# HHO.net
KiCad netlist of a schematic drawn in Altium Designer
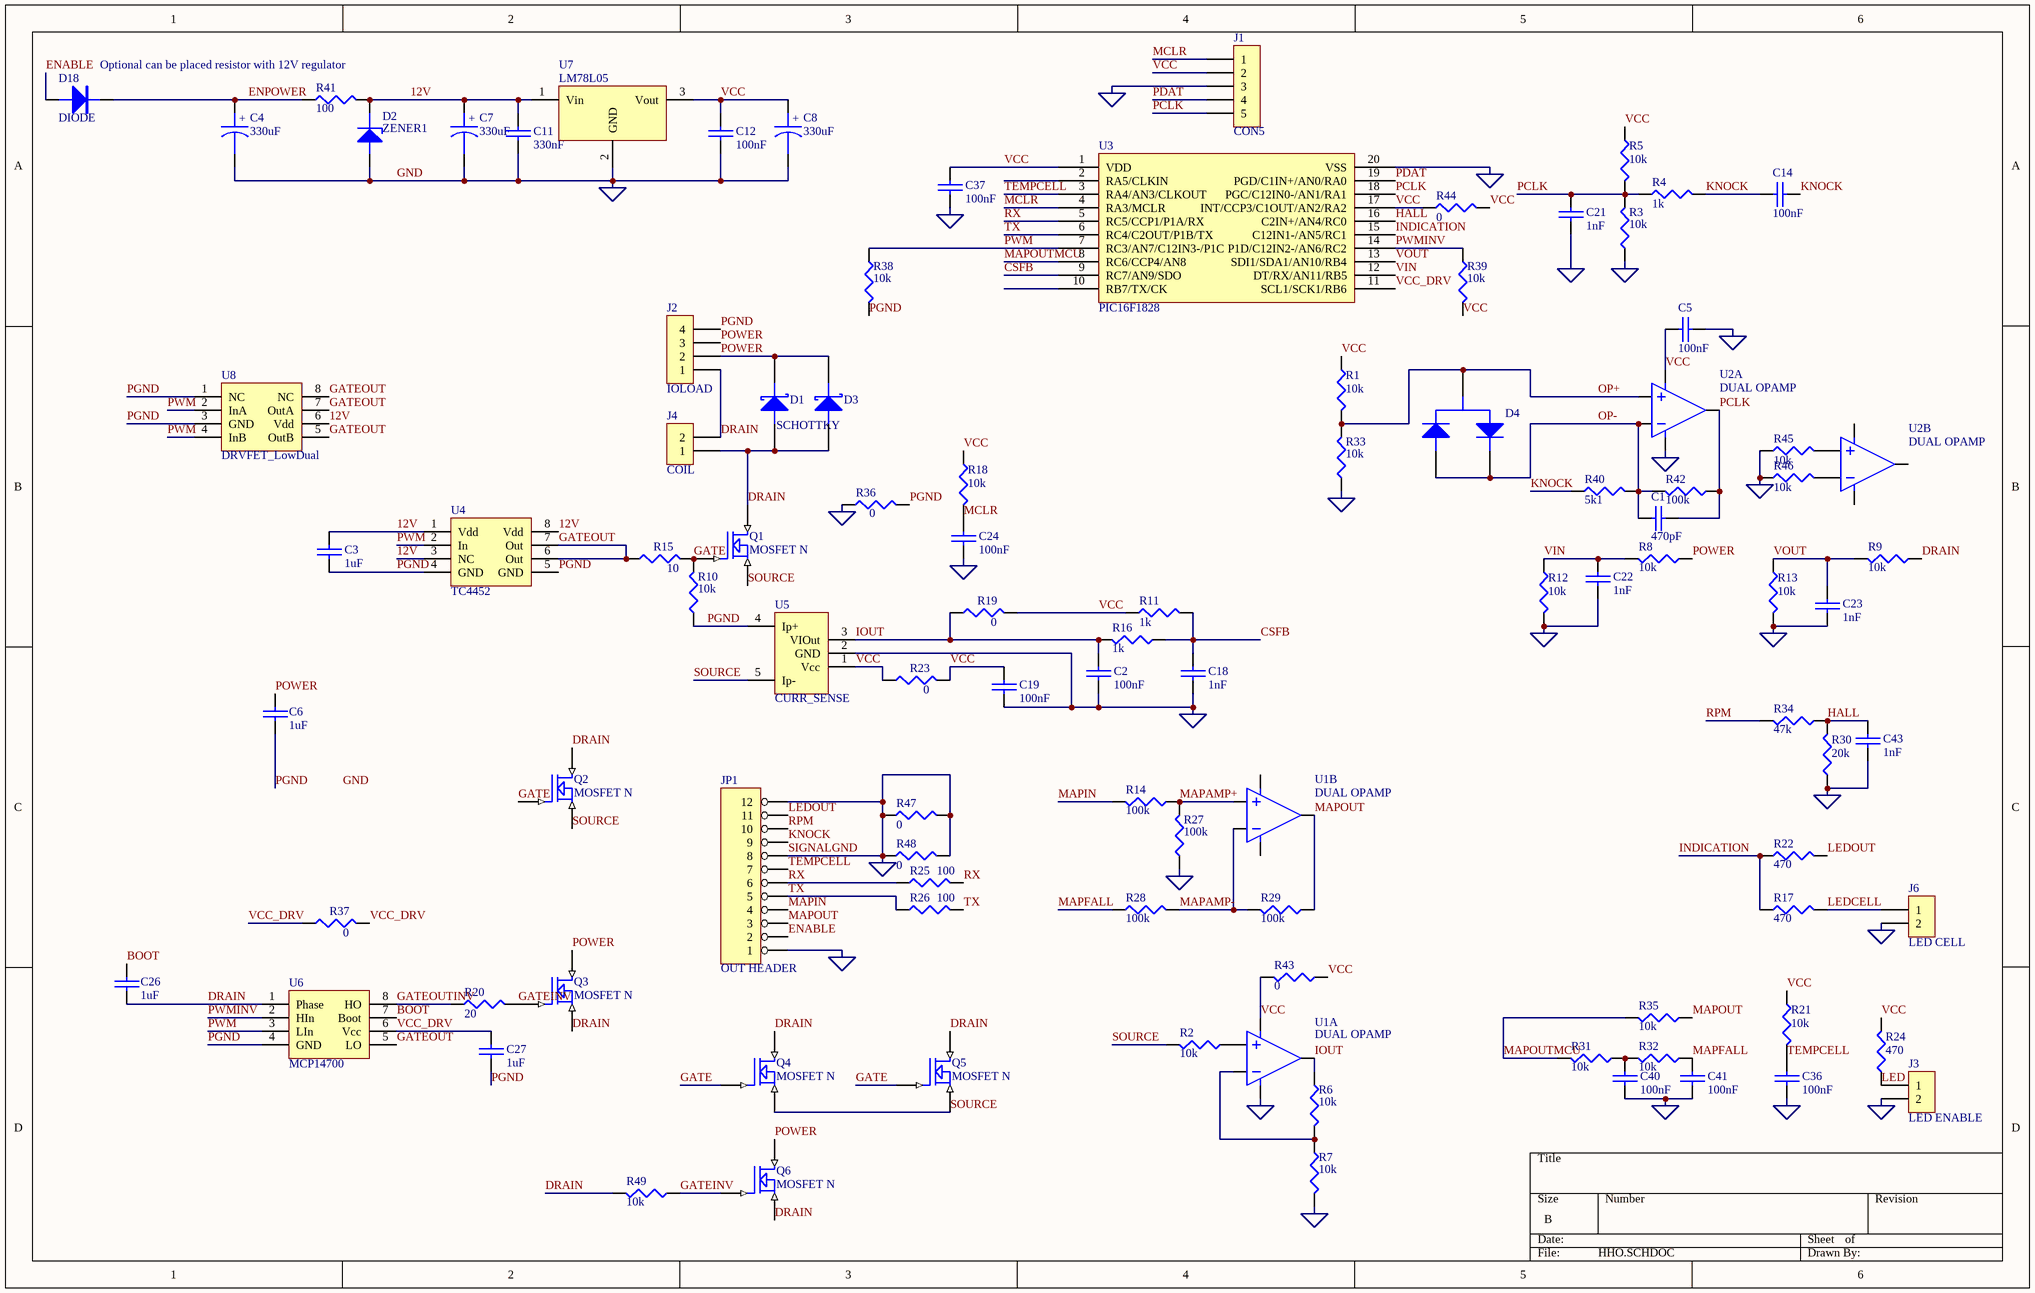
[diagram p0: HHO.SCHDOC]

(export (version "E")
  (design (tool "Eeschema 10.0.6"))
  (components
    (comp (ref "C1")
      (value "470pF")
      (footprint "0603 CAP")
      (description "Capacitor")
      (libsource (lib "*") (part "CAP"))
    )
    (comp (ref "C2")
      (value "100nF")
      (footprint "0603 CAP")
      (description "Capacitor")
      (libsource (lib "*") (part "CAP"))
    )
    (comp (ref "C3")
      (value "1uF")
      (footprint "0805")
      (description "Capacitor")
      (libsource (lib "*") (part "CAP"))
    )
    (comp (ref "C4")
      (value "330uF")
      (footprint "RA 6.3MM")
      (description "Capacitor")
      (libsource (lib "*") (part "CAPACITOR POL"))
    )
    (comp (ref "C5")
      (value "100nF")
      (footprint "0603 CAP")
      (description "Capacitor")
      (libsource (lib "*") (part "CAP"))
    )
    (comp (ref "C6")
      (value "1uF")
      (footprint "1210")
      (description "Capacitor")
      (libsource (lib "*") (part "CAP"))
    )
    (comp (ref "C7")
      (value "330uF")
      (footprint "3528 + RA 6.3mm NOT ROUND")
      (description "Capacitor")
      (libsource (lib "*") (part "CAPACITOR POL"))
    )
    (comp (ref "C8")
      (value "330uF")
      (footprint "3528 + RA 6.3mm NOT ROUND")
      (description "Capacitor")
      (libsource (lib "*") (part "CAPACITOR POL"))
    )
    (comp (ref "C11")
      (value "330nF")
      (footprint "0805")
      (description "Capacitor")
      (libsource (lib "*") (part "CAP"))
    )
    (comp (ref "C12")
      (value "100nF")
      (footprint "0805")
      (description "Capacitor")
      (libsource (lib "*") (part "CAP"))
    )
    (comp (ref "C14")
      (value "100nF")
      (footprint "0603 CAP")
      (description "Capacitor")
      (libsource (lib "*") (part "CAP"))
    )
    (comp (ref "C18")
      (value "1nF")
      (footprint "0603 CAP")
      (description "Capacitor")
      (libsource (lib "*") (part "CAP"))
    )
    (comp (ref "C19")
      (value "100nF")
      (footprint "0603 CAP")
      (description "Capacitor")
      (libsource (lib "*") (part "CAP"))
    )
    (comp (ref "C21")
      (value "1nF")
      (footprint "0603 CAP")
      (description "Capacitor")
      (libsource (lib "*") (part "CAP"))
    )
    (comp (ref "C22")
      (value "1nF")
      (footprint "0603 CAP")
      (description "Capacitor")
      (libsource (lib "*") (part "CAP"))
    )
    (comp (ref "C23")
      (value "1nF")
      (footprint "0603 CAP")
      (description "Capacitor")
      (libsource (lib "*") (part "CAP"))
    )
    (comp (ref "C24")
      (value "100nF")
      (footprint "0603 CAP")
      (description "Capacitor")
      (libsource (lib "*") (part "CAP"))
    )
    (comp (ref "C26")
      (value "1uF")
      (footprint "0805")
      (description "Capacitor")
      (libsource (lib "*") (part "CAP"))
    )
    (comp (ref "C27")
      (value "1uF")
      (footprint "1005")
      (description "Capacitor")
      (libsource (lib "*") (part "CAP"))
    )
    (comp (ref "C36")
      (value "100nF")
      (footprint "0603 CAP")
      (description "Capacitor")
      (libsource (lib "*") (part "CAP"))
    )
    (comp (ref "C37")
      (value "100nF")
      (footprint "0603 CAP")
      (description "Capacitor")
      (libsource (lib "*") (part "CAP"))
    )
    (comp (ref "C40")
      (value "100nF")
      (footprint "0603 CAP")
      (description "Capacitor")
      (libsource (lib "*") (part "CAP"))
    )
    (comp (ref "C41")
      (value "100nF")
      (footprint "0603 CAP")
      (description "Capacitor")
      (libsource (lib "*") (part "CAP"))
    )
    (comp (ref "C43")
      (value "1nF")
      (footprint "0603 CAP")
      (description "Capacitor")
      (libsource (lib "*") (part "CAP"))
    )
    (comp (ref "D1")
      (value "SCHOTTKY")
      (footprint "D2-Pack - 3 - DIODE")
      (description "Schottky Diode")
      (libsource (lib "Miscellaneous Devices") (part "DIODE SCHOTTKY"))
    )
    (comp (ref "D2")
      (value "ZENER1")
      (footprint "SIP2")
      (description "Zener Diode")
      (libsource (lib "Miscellaneous Devices") (part "ZENER1"))
    )
    (comp (ref "D3")
      (value "~")
      (footprint "D2-Pack - 3 - DIODE")
      (description "Schottky Diode")
      (libsource (lib "Miscellaneous Devices") (part "DIODE SCHOTTKY"))
    )
    (comp (ref "D4")
      (value "DUAL DIODE BAV99")
      (footprint "SOT-23")
      (libsource (lib "Devices") (part "DUAL DIODE BAV99"))
    )
    (comp (ref "D18")
      (value "DIODE")
      (footprint "SIP2")
      (description "Diode")
      (libsource (lib "Miscellaneous Devices") (part "DIODE"))
    )
    (comp (ref "J1")
      (value "CON5")
      (footprint "SIP5")
      (description "Connector")
      (libsource (lib "Miscellaneous Devices") (part "CON5"))
    )
    (comp (ref "J2")
      (value "IOLOAD")
      (footprint "HD 11mm 4P HAMMOND")
      (description "Connector")
      (libsource (lib "Miscellaneous Devices") (part "CON4"))
    )
    (comp (ref "J3")
      (value "LED ENABLE")
      (footprint "SIP2")
      (description "Connector")
      (libsource (lib "Miscellaneous Devices") (part "CON2"))
    )
    (comp (ref "J4")
      (value "COIL")
      (footprint "SIP2 - INDUCTOR 20A")
      (description "Connector")
      (libsource (lib "") (part "CON2_1"))
    )
    (comp (ref "J6")
      (value "LED CELL")
      (footprint "SIP2")
      (description "Connector")
      (libsource (lib "Miscellaneous Devices") (part "CON2"))
    )
    (comp (ref "JP1")
      (value "OUT HEADER")
      (footprint "PWD12R")
      (description "12 Pin Header")
      (libsource (lib "Miscellaneous Devices") (part "12 HEADER"))
    )
    (comp (ref "Q1")
      (value "MOSFET N")
      (footprint "D2-Pack - 7")
      (libsource (lib "Miscellaneous Devices") (part "MOSFET N"))
    )
    (comp (ref "Q2")
      (value "MOSFET N")
      (footprint "D2-Pack - 7")
      (libsource (lib "Miscellaneous Devices") (part "MOSFET N"))
    )
    (comp (ref "Q3")
      (value "MOSFET N")
      (footprint "D2-Pack - 7")
      (libsource (lib "Miscellaneous Devices") (part "MOSFET N"))
    )
    (comp (ref "Q4")
      (value "MOSFET N")
      (footprint "TO220")
      (libsource (lib "Miscellaneous Devices") (part "MOSFET N"))
    )
    (comp (ref "Q5")
      (value "MOSFET N")
      (footprint "TO220")
      (libsource (lib "Miscellaneous Devices") (part "MOSFET N"))
    )
    (comp (ref "Q6")
      (value "MOSFET N")
      (footprint "TO220")
      (libsource (lib "Miscellaneous Devices") (part "MOSFET N"))
    )
    (comp (ref "R1") (value "10k") (footprint "1005") (libsource (lib "Miscellaneous Devices") (part "RES1")))
    (comp (ref "R2")
      (value "10k")
      (footprint "0603 RES")
      (libsource (lib "Miscellaneous Devices") (part "RES1"))
    )
    (comp (ref "R3")
      (value "10k")
      (footprint "0603 RES")
      (libsource (lib "Miscellaneous Devices") (part "RES1"))
    )
    (comp (ref "R4")
      (value "1k")
      (footprint "0603 RES")
      (libsource (lib "Miscellaneous Devices") (part "RES1"))
    )
    (comp (ref "R5")
      (value "10k")
      (footprint "0603 RES")
      (libsource (lib "Miscellaneous Devices") (part "RES1"))
    )
    (comp (ref "R6")
      (value "10k")
      (footprint "0603 RES")
      (libsource (lib "Miscellaneous Devices") (part "RES1"))
    )
    (comp (ref "R7")
      (value "10k")
      (footprint "0603 RES")
      (libsource (lib "Miscellaneous Devices") (part "RES1"))
    )
    (comp (ref "R8")
      (value "10k")
      (footprint "0603 RES")
      (libsource (lib "Miscellaneous Devices") (part "RES1"))
    )
    (comp (ref "R9") (value "10k") (footprint "1005") (libsource (lib "Miscellaneous Devices") (part "RES1")))
    (comp (ref "R10")
      (value "10k")
      (footprint "0603 RES")
      (libsource (lib "Miscellaneous Devices") (part "RES1"))
    )
    (comp (ref "R11")
      (value "1k")
      (footprint "0603 RES")
      (libsource (lib "Miscellaneous Devices") (part "RES1"))
    )
    (comp (ref "R12")
      (value "10k")
      (footprint "0603 RES")
      (libsource (lib "Miscellaneous Devices") (part "RES1"))
    )
    (comp (ref "R13")
      (value "10k")
      (footprint "0603")
      (libsource (lib "Miscellaneous Devices") (part "RES1"))
    )
    (comp (ref "R14")
      (value "100k")
      (footprint "0603 RES")
      (libsource (lib "Miscellaneous Devices") (part "RES1"))
    )
    (comp (ref "R15")
      (value "10")
      (footprint "0603 RES")
      (libsource (lib "Miscellaneous Devices") (part "RES1"))
    )
    (comp (ref "R16")
      (value "1k")
      (footprint "0603 RES")
      (libsource (lib "Miscellaneous Devices") (part "RES1"))
    )
    (comp (ref "R17")
      (value "470")
      (footprint "0603 RES")
      (libsource (lib "Miscellaneous Devices") (part "RES1"))
    )
    (comp (ref "R18")
      (value "10k")
      (footprint "0603 RES")
      (libsource (lib "Miscellaneous Devices") (part "RES1"))
    )
    (comp (ref "R19")
      (value "0")
      (footprint "0603 RES")
      (libsource (lib "Miscellaneous Devices") (part "RES1"))
    )
    (comp (ref "R20")
      (value "20")
      (footprint "0603 RES")
      (libsource (lib "Miscellaneous Devices") (part "RES1"))
    )
    (comp (ref "R21")
      (value "10k")
      (footprint "0603 RES")
      (libsource (lib "Miscellaneous Devices") (part "RES1"))
    )
    (comp (ref "R22")
      (value "470")
      (footprint "0603 RES")
      (libsource (lib "Miscellaneous Devices") (part "RES1"))
    )
    (comp (ref "R23")
      (value "0")
      (footprint "0603 RES")
      (libsource (lib "Miscellaneous Devices") (part "RES1"))
    )
    (comp (ref "R24")
      (value "470")
      (footprint "0603 RES")
      (libsource (lib "Miscellaneous Devices") (part "RES1"))
    )
    (comp (ref "R25")
      (value "100")
      (footprint "0603 RES")
      (libsource (lib "Miscellaneous Devices") (part "RES1"))
    )
    (comp (ref "R26")
      (value "100")
      (footprint "0603 RES")
      (libsource (lib "Miscellaneous Devices") (part "RES1"))
    )
    (comp (ref "R27")
      (value "100k")
      (footprint "0603 RES")
      (libsource (lib "Miscellaneous Devices") (part "RES1"))
    )
    (comp (ref "R28")
      (value "100k")
      (footprint "0603 RES")
      (libsource (lib "Miscellaneous Devices") (part "RES1"))
    )
    (comp (ref "R29")
      (value "100k")
      (footprint "0603 RES")
      (libsource (lib "Miscellaneous Devices") (part "RES1"))
    )
    (comp (ref "R30")
      (value "20k")
      (footprint "0603 RES")
      (libsource (lib "Miscellaneous Devices") (part "RES1"))
    )
    (comp (ref "R31")
      (value "10k")
      (footprint "0603 RES")
      (libsource (lib "Miscellaneous Devices") (part "RES1"))
    )
    (comp (ref "R32")
      (value "10k")
      (footprint "0603 RES")
      (libsource (lib "Miscellaneous Devices") (part "RES1"))
    )
    (comp (ref "R33")
      (value "10k")
      (footprint "0603 RES")
      (libsource (lib "Miscellaneous Devices") (part "RES1"))
    )
    (comp (ref "R34")
      (value "47k")
      (footprint "0603 RES")
      (libsource (lib "Miscellaneous Devices") (part "RES1"))
    )
    (comp (ref "R35")
      (value "10k")
      (footprint "0603 RES")
      (libsource (lib "Miscellaneous Devices") (part "RES1"))
    )
    (comp (ref "R36") (value "0") (footprint "0805") (libsource (lib "Miscellaneous Devices") (part "RES1")))
    (comp (ref "R37")
      (value "0")
      (footprint "0603 RES")
      (libsource (lib "Miscellaneous Devices") (part "RES1"))
    )
    (comp (ref "R38")
      (value "10k")
      (footprint "0603 RES")
      (libsource (lib "Miscellaneous Devices") (part "RES1"))
    )
    (comp (ref "R39")
      (value "10k")
      (footprint "0603 RES")
      (libsource (lib "Miscellaneous Devices") (part "RES1"))
    )
    (comp (ref "R40")
      (value "5k1")
      (footprint "0603 RES")
      (libsource (lib "Miscellaneous Devices") (part "RES1"))
    )
    (comp (ref "R41")
      (value "100")
      (footprint "0805")
      (libsource (lib "Miscellaneous Devices") (part "RES1"))
    )
    (comp (ref "R42")
      (value "100k")
      (footprint "0603 RES")
      (libsource (lib "Miscellaneous Devices") (part "RES1"))
    )
    (comp (ref "R43")
      (value "0")
      (footprint "0603 RES")
      (libsource (lib "Miscellaneous Devices") (part "RES1"))
    )
    (comp (ref "R44")
      (value "0")
      (footprint "0603 RES")
      (libsource (lib "Miscellaneous Devices") (part "RES1"))
    )
    (comp (ref "R45")
      (value "10k")
      (footprint "0603 RES")
      (libsource (lib "Miscellaneous Devices") (part "RES1"))
    )
    (comp (ref "R46")
      (value "10k")
      (footprint "0603 RES")
      (libsource (lib "Miscellaneous Devices") (part "RES1"))
    )
    (comp (ref "R47")
      (value "0")
      (footprint "0603 RES")
      (libsource (lib "Miscellaneous Devices") (part "RES1"))
    )
    (comp (ref "R48")
      (value "0")
      (footprint "0603 RES")
      (libsource (lib "Miscellaneous Devices") (part "RES1"))
    )
    (comp (ref "R49")
      (value "10k")
      (footprint "0603 RES")
      (libsource (lib "Miscellaneous Devices") (part "RES1"))
    )
    (comp (ref "U1") (value "DUAL OPAMP") (footprint "SO-8") (libsource (lib "Devices") (part "DUAL OPAMP")))
    (comp (ref "U2") (value "DUAL OPAMP") (footprint "SO-8") (libsource (lib "Devices") (part "DUAL OPAMP")))
    (comp (ref "U3")
      (value "PIC16F1828")
      (footprint "SOIC20WIDE")
      (description "Microchip Microcontroller")
      (libsource (lib "MCU") (part "PIC16F1828"))
    )
    (comp (ref "U4")
      (value "TC4452")
      (footprint "SO-8")
      (description "Mosfet Low Side Single driver")
      (libsource (lib "Devices") (part "DRVFET_LowSingle"))
    )
    (comp (ref "U5")
      (value "CURR_SENSE")
      (footprint "5-CB WIDE")
      (description "Current Sense Hall")
      (libsource (lib "Devices") (part "CURR_SENSE"))
    )
    (comp (ref "U6")
      (value "MCP14700")
      (footprint "SO-8")
      (description "Mosfet High and Low Side driver")
      (libsource (lib "Devices") (part "DRVFET_14700"))
    )
    (comp (ref "U7") (value "LM78L05") (footprint "TO-92 WIDE") (libsource (lib "*") (part "VOLTREG")))
    (comp (ref "U8")
      (value "DRVFET_LowDual")
      (footprint "SO-8")
      (description "Mosfet Low Side Dual driver")
      (libsource (lib "Devices") (part "DRVFET_LowDual"))
    )
  )
  (nets
    (net (code "1") (name "/12V") (class "Default")
      (node (ref "C11") (pin "1") (pinfunction "1_1") (pintype "passive"))
      (node (ref "C3") (pin "1") (pinfunction "1_1") (pintype "passive"))
      (node (ref "C7") (pin "1") (pinfunction "1_1") (pintype "passive"))
      (node (ref "D2") (pin "2") (pinfunction "K_2") (pintype "passive"))
      (node (ref "R41") (pin "2") (pinfunction "2_2") (pintype "passive"))
      (node (ref "U4") (pin "1") (pinfunction "Vdd_1") (pintype "passive"))
      (node (ref "U4") (pin "3") (pinfunction "NC_3") (pintype "passive"))
      (node (ref "U4") (pin "8") (pinfunction "Vdd_8") (pintype "passive"))
      (node (ref "U7") (pin "1") (pinfunction "Vin_1") (pintype "passive"))
      (node (ref "U8") (pin "6") (pinfunction "Vdd_6") (pintype "passive"))
    )
    (net (code "2") (name "/BOOT") (class "Default")
      (node (ref "C26") (pin "1") (pinfunction "1_1") (pintype "passive"))
      (node (ref "U6") (pin "7") (pinfunction "Boot_7") (pintype "passive"))
    )
    (net (code "3") (name "/CSFB") (class "Default")
      (node (ref "C18") (pin "1") (pinfunction "1_1") (pintype "passive"))
      (node (ref "R11") (pin "2") (pinfunction "2_2") (pintype "passive"))
      (node (ref "R16") (pin "1") (pinfunction "1_1") (pintype "passive"))
      (node (ref "U3") (pin "9") (pinfunction "RC7/AN9/SDO_9") (pintype "passive"))
    )
    (net (code "4") (name "/DRAIN") (class "Default")
      (node (ref "C26") (pin "2") (pinfunction "2_2") (pintype "passive"))
      (node (ref "D1") (pin "1") (pinfunction "A_1") (pintype "passive"))
      (node (ref "D3") (pin "1") (pinfunction "A_1") (pintype "passive"))
      (node (ref "J2") (pin "1") (pinfunction "1_1") (pintype "passive"))
      (node (ref "J4") (pin "1") (pinfunction "1_1") (pintype "passive"))
      (node (ref "J4") (pin "2") (pinfunction "2_2") (pintype "passive"))
      (node (ref "Q1") (pin "2") (pinfunction "D_2") (pintype "input"))
      (node (ref "Q2") (pin "2") (pinfunction "D_2") (pintype "input"))
      (node (ref "Q3") (pin "3") (pinfunction "S_3") (pintype "input"))
      (node (ref "Q4") (pin "2") (pinfunction "D_2") (pintype "input"))
      (node (ref "Q5") (pin "2") (pinfunction "D_2") (pintype "input"))
      (node (ref "Q6") (pin "3") (pinfunction "S_3") (pintype "input"))
      (node (ref "R49") (pin "2") (pinfunction "2_2") (pintype "passive"))
      (node (ref "R9") (pin "1") (pinfunction "1_1") (pintype "passive"))
      (node (ref "U6") (pin "1") (pinfunction "Phase_1") (pintype "passive"))
    )
    (net (code "5") (name "/ENABLE") (class "Default")
      (node (ref "D18") (pin "1") (pinfunction "A_1") (pintype "passive"))
      (node (ref "JP1") (pin "2") (pinfunction "2_2") (pintype "passive"))
    )
    (net (code "6") (name "/ENPOWER") (class "Default")
      (node (ref "C4") (pin "1") (pinfunction "1_1") (pintype "passive"))
      (node (ref "D18") (pin "2") (pinfunction "K_2") (pintype "passive"))
      (node (ref "R41") (pin "1") (pinfunction "1_1") (pintype "passive"))
    )
    (net (code "7") (name "/GATE") (class "Default")
      (node (ref "Q1") (pin "1") (pinfunction "G_1") (pintype "input"))
      (node (ref "Q2") (pin "1") (pinfunction "G_1") (pintype "input"))
      (node (ref "Q4") (pin "1") (pinfunction "G_1") (pintype "input"))
      (node (ref "Q5") (pin "1") (pinfunction "G_1") (pintype "input"))
      (node (ref "R10") (pin "2") (pinfunction "2_2") (pintype "passive"))
      (node (ref "R15") (pin "2") (pinfunction "2_2") (pintype "passive"))
    )
    (net (code "8") (name "/GATEINV") (class "Default")
      (node (ref "Q3") (pin "1") (pinfunction "G_1") (pintype "input"))
      (node (ref "Q6") (pin "1") (pinfunction "G_1") (pintype "input"))
      (node (ref "R20") (pin "2") (pinfunction "2_2") (pintype "passive"))
      (node (ref "R49") (pin "1") (pinfunction "1_1") (pintype "passive"))
    )
    (net (code "9") (name "/GATEOUT") (class "Default")
      (node (ref "R15") (pin "1") (pinfunction "1_1") (pintype "passive"))
      (node (ref "U4") (pin "6") (pinfunction "Out_6") (pintype "passive"))
      (node (ref "U4") (pin "7") (pinfunction "Out_7") (pintype "passive"))
      (node (ref "U6") (pin "5") (pinfunction "LO_5") (pintype "passive"))
      (node (ref "U8") (pin "5") (pinfunction "OutB_5") (pintype "passive"))
      (node (ref "U8") (pin "7") (pinfunction "OutA_7") (pintype "passive"))
      (node (ref "U8") (pin "8") (pinfunction "NC_8") (pintype "passive"))
    )
    (net (code "10") (name "/GATEOUTINV") (class "Default")
      (node (ref "R20") (pin "1") (pinfunction "1_1") (pintype "passive"))
      (node (ref "U6") (pin "8") (pinfunction "HO_8") (pintype "passive"))
    )
    (net (code "11") (name "/HALL") (class "Default")
      (node (ref "C43") (pin "1") (pinfunction "1_1") (pintype "passive"))
      (node (ref "R30") (pin "2") (pinfunction "2_2") (pintype "passive"))
      (node (ref "R34") (pin "1") (pinfunction "1_1") (pintype "passive"))
      (node (ref "U3") (pin "16") (pinfunction "C2IN+/AN4/RC0_16") (pintype "passive"))
    )
    (net (code "12") (name "/INDICATION") (class "Default")
      (node (ref "R17") (pin "1") (pinfunction "1_1") (pintype "passive"))
      (node (ref "R22") (pin "1") (pinfunction "1_1") (pintype "passive"))
      (node (ref "U3") (pin "15") (pinfunction "C12IN1-/AN5/RC1_15") (pintype "passive"))
    )
    (net (code "13") (name "/IOUT") (class "Default")
      (node (ref "C2") (pin "1") (pinfunction "1_1") (pintype "passive"))
      (node (ref "R16") (pin "2") (pinfunction "2_2") (pintype "passive"))
      (node (ref "R19") (pin "1") (pinfunction "1_1") (pintype "passive"))
      (node (ref "R6") (pin "1") (pinfunction "1_1") (pintype "passive"))
      (node (ref "U1") (pin "1") (pinfunction "OUT_1") (pintype "passive"))
      (node (ref "U5") (pin "3") (pinfunction "VIOut_3") (pintype "passive"))
    )
    (net (code "14") (name "/KNOCK") (class "Default")
      (node (ref "C14") (pin "1") (pinfunction "1_1") (pintype "passive"))
      (node (ref "C14") (pin "2") (pinfunction "2_2") (pintype "passive"))
      (node (ref "JP1") (pin "9") (pinfunction "9_9") (pintype "passive"))
      (node (ref "R4") (pin "2") (pinfunction "2_2") (pintype "passive"))
      (node (ref "R40") (pin "1") (pinfunction "1_1") (pintype "passive"))
    )
    (net (code "15") (name "/LED") (class "Default")
      (node (ref "J3") (pin "1") (pinfunction "1_1") (pintype "passive"))
      (node (ref "R24") (pin "1") (pinfunction "1_1") (pintype "passive"))
    )
    (net (code "16") (name "/LEDCELL") (class "Default")
      (node (ref "J6") (pin "1") (pinfunction "1_1") (pintype "passive"))
      (node (ref "R17") (pin "2") (pinfunction "2_2") (pintype "passive"))
    )
    (net (code "17") (name "/LEDOUT") (class "Default")
      (node (ref "JP1") (pin "11") (pinfunction "11_11") (pintype "passive"))
      (node (ref "R22") (pin "2") (pinfunction "2_2") (pintype "passive"))
    )
    (net (code "18") (name "/MAPAMP+") (class "Default")
      (node (ref "R14") (pin "1") (pinfunction "1_1") (pintype "passive"))
      (node (ref "R27") (pin "2") (pinfunction "2_2") (pintype "passive"))
      (node (ref "U1") (pin "5") (pinfunction "IN+_5") (pintype "passive"))
    )
    (net (code "19") (name "/MAPAMP-") (class "Default")
      (node (ref "R28") (pin "2") (pinfunction "2_2") (pintype "passive"))
      (node (ref "R29") (pin "2") (pinfunction "2_2") (pintype "passive"))
      (node (ref "U1") (pin "6") (pinfunction "IN-_6") (pintype "passive"))
    )
    (net (code "20") (name "/MAPFALL") (class "Default")
      (node (ref "C41") (pin "1") (pinfunction "1_1") (pintype "passive"))
      (node (ref "R28") (pin "1") (pinfunction "1_1") (pintype "passive"))
      (node (ref "R32") (pin "1") (pinfunction "1_1") (pintype "passive"))
    )
    (net (code "21") (name "/MAPIN") (class "Default")
      (node (ref "JP1") (pin "4") (pinfunction "4_4") (pintype "passive"))
      (node (ref "R14") (pin "2") (pinfunction "2_2") (pintype "passive"))
    )
    (net (code "22") (name "/MAPOUT") (class "Default")
      (node (ref "JP1") (pin "3") (pinfunction "3_3") (pintype "passive"))
      (node (ref "R29") (pin "1") (pinfunction "1_1") (pintype "passive"))
      (node (ref "R35") (pin "1") (pinfunction "1_1") (pintype "passive"))
      (node (ref "U1") (pin "7") (pinfunction "OUT_7") (pintype "passive"))
    )
    (net (code "23") (name "/MAPOUTMCU") (class "Default")
      (node (ref "R31") (pin "2") (pinfunction "2_2") (pintype "passive"))
      (node (ref "R35") (pin "2") (pinfunction "2_2") (pintype "passive"))
      (node (ref "U3") (pin "8") (pinfunction "RC6/CCP4/AN8_8") (pintype "passive"))
    )
    (net (code "24") (name "/MCLR") (class "Default")
      (node (ref "C24") (pin "1") (pinfunction "1_1") (pintype "passive"))
      (node (ref "J1") (pin "1") (pinfunction "1_1") (pintype "passive"))
      (node (ref "R18") (pin "2") (pinfunction "2_2") (pintype "passive"))
      (node (ref "U3") (pin "4") (pinfunction "RA3/MCLR_4") (pintype "passive"))
    )
    (net (code "25") (name "/OP+") (class "Default")
      (node (ref "D4") (pin "2") (pinfunction "AK_2") (pintype "passive"))
      (node (ref "R1") (pin "2") (pinfunction "2_2") (pintype "passive"))
      (node (ref "R33") (pin "2") (pinfunction "2_2") (pintype "passive"))
      (node (ref "U2") (pin "3") (pinfunction "IN+_3") (pintype "passive"))
    )
    (net (code "26") (name "/OP-") (class "Default")
      (node (ref "C1") (pin "1") (pinfunction "1_1") (pintype "passive"))
      (node (ref "D4") (pin "1") (pinfunction "A_1") (pintype "passive"))
      (node (ref "D4") (pin "3") (pinfunction "K_3") (pintype "passive"))
      (node (ref "R40") (pin "2") (pinfunction "2_2") (pintype "passive"))
      (node (ref "R42") (pin "2") (pinfunction "2_2") (pintype "passive"))
      (node (ref "U2") (pin "2") (pinfunction "IN-_2") (pintype "passive"))
    )
    (net (code "27") (name "/PCLK") (class "Default")
      (node (ref "C1") (pin "2") (pinfunction "2_2") (pintype "passive"))
      (node (ref "C21") (pin "1") (pinfunction "1_1") (pintype "passive"))
      (node (ref "J1") (pin "5") (pinfunction "5_5") (pintype "passive"))
      (node (ref "R3") (pin "2") (pinfunction "2_2") (pintype "passive"))
      (node (ref "R4") (pin "1") (pinfunction "1_1") (pintype "passive"))
      (node (ref "R42") (pin "1") (pinfunction "1_1") (pintype "passive"))
      (node (ref "R5") (pin "2") (pinfunction "2_2") (pintype "passive"))
      (node (ref "U2") (pin "1") (pinfunction "OUT_1") (pintype "passive"))
      (node (ref "U3") (pin "18") (pinfunction "PGC/C12IN0-/AN1/RA1_18") (pintype "passive"))
    )
    (net (code "28") (name "/PDAT") (class "Default")
      (node (ref "J1") (pin "4") (pinfunction "4_4") (pintype "passive"))
      (node (ref "U3") (pin "19") (pinfunction "PGD/C1IN+/AN0/RA0_19") (pintype "passive"))
    )
    (net (code "29") (name "/PGND") (class "Default")
      (node (ref "C27") (pin "2") (pinfunction "2_2") (pintype "passive"))
      (node (ref "C3") (pin "2") (pinfunction "2_2") (pintype "passive"))
      (node (ref "C6") (pin "2") (pinfunction "2_2") (pintype "passive"))
      (node (ref "J2") (pin "4") (pinfunction "4_4") (pintype "passive"))
      (node (ref "R10") (pin "1") (pinfunction "1_1") (pintype "passive"))
      (node (ref "R36") (pin "2") (pinfunction "2_2") (pintype "passive"))
      (node (ref "R38") (pin "2") (pinfunction "2_2") (pintype "passive"))
      (node (ref "U4") (pin "4") (pinfunction "GND_4") (pintype "passive"))
      (node (ref "U4") (pin "5") (pinfunction "GND_5") (pintype "passive"))
      (node (ref "U5") (pin "4") (pinfunction "Ip+_4") (pintype "passive"))
      (node (ref "U6") (pin "4") (pinfunction "GND_4") (pintype "passive"))
      (node (ref "U8") (pin "1") (pinfunction "NC_1") (pintype "passive"))
      (node (ref "U8") (pin "3") (pinfunction "GND_3") (pintype "passive"))
    )
    (net (code "30") (name "/POWER") (class "Default")
      (node (ref "C6") (pin "1") (pinfunction "1_1") (pintype "passive"))
      (node (ref "D1") (pin "2") (pinfunction "K_2") (pintype "passive"))
      (node (ref "D3") (pin "2") (pinfunction "K_2") (pintype "passive"))
      (node (ref "J2") (pin "2") (pinfunction "2_2") (pintype "passive"))
      (node (ref "J2") (pin "3") (pinfunction "3_3") (pintype "passive"))
      (node (ref "Q3") (pin "2") (pinfunction "D_2") (pintype "input"))
      (node (ref "Q6") (pin "2") (pinfunction "D_2") (pintype "input"))
      (node (ref "R8") (pin "1") (pinfunction "1_1") (pintype "passive"))
    )
    (net (code "31") (name "/PWM") (class "Default")
      (node (ref "R38") (pin "1") (pinfunction "1_1") (pintype "passive"))
      (node (ref "U3") (pin "7") (pinfunction "RC3/AN7/C12IN3-/P1C_7") (pintype "passive"))
      (node (ref "U4") (pin "2") (pinfunction "In_2") (pintype "passive"))
      (node (ref "U6") (pin "3") (pinfunction "LIn_3") (pintype "passive"))
      (node (ref "U8") (pin "2") (pinfunction "InA_2") (pintype "passive"))
      (node (ref "U8") (pin "4") (pinfunction "InB_4") (pintype "passive"))
    )
    (net (code "32") (name "/PWMINV") (class "Default")
      (node (ref "R39") (pin "1") (pinfunction "1_1") (pintype "passive"))
      (node (ref "U3") (pin "14") (pinfunction "P1D/C12IN2-/AN6/RC2_14") (pintype "passive"))
      (node (ref "U6") (pin "2") (pinfunction "HIn_2") (pintype "passive"))
    )
    (net (code "33") (name "/RPM") (class "Default")
      (node (ref "JP1") (pin "10") (pinfunction "10_10") (pintype "passive"))
      (node (ref "R34") (pin "2") (pinfunction "2_2") (pintype "passive"))
    )
    (net (code "34") (name "/RX") (class "Default")
      (node (ref "JP1") (pin "6") (pinfunction "6_6") (pintype "passive"))
      (node (ref "R25") (pin "1") (pinfunction "1_1") (pintype "passive"))
      (node (ref "R25") (pin "2") (pinfunction "2_2") (pintype "passive"))
      (node (ref "U3") (pin "5") (pinfunction "RC5/CCP1/P1A/RX_5") (pintype "passive"))
    )
    (net (code "35") (name "/SOURCE") (class "Default")
      (node (ref "Q1") (pin "3") (pinfunction "S_3") (pintype "input"))
      (node (ref "Q2") (pin "3") (pinfunction "S_3") (pintype "input"))
      (node (ref "Q4") (pin "3") (pinfunction "S_3") (pintype "input"))
      (node (ref "Q5") (pin "3") (pinfunction "S_3") (pintype "input"))
      (node (ref "R2") (pin "2") (pinfunction "2_2") (pintype "passive"))
      (node (ref "U5") (pin "5") (pinfunction "Ip-_5") (pintype "passive"))
    )
    (net (code "36") (name "/TEMPCELL") (class "Default")
      (node (ref "C36") (pin "1") (pinfunction "1_1") (pintype "passive"))
      (node (ref "JP1") (pin "7") (pinfunction "7_7") (pintype "passive"))
      (node (ref "R21") (pin "2") (pinfunction "2_2") (pintype "passive"))
      (node (ref "U3") (pin "3") (pinfunction "RA4/AN3/CLKOUT_3") (pintype "passive"))
    )
    (net (code "37") (name "/TX") (class "Default")
      (node (ref "JP1") (pin "5") (pinfunction "5_5") (pintype "passive"))
      (node (ref "R26") (pin "1") (pinfunction "1_1") (pintype "passive"))
      (node (ref "R26") (pin "2") (pinfunction "2_2") (pintype "passive"))
      (node (ref "U3") (pin "6") (pinfunction "RC4/C2OUT/P1B/TX_6") (pintype "passive"))
    )
    (net (code "38") (name "/VCC") (class "Default")
      (node (ref "C12") (pin "1") (pinfunction "1_1") (pintype "passive"))
      (node (ref "C19") (pin "1") (pinfunction "1_1") (pintype "passive"))
      (node (ref "C37") (pin "1") (pinfunction "1_1") (pintype "passive"))
      (node (ref "C5") (pin "2") (pinfunction "2_2") (pintype "passive"))
      (node (ref "C8") (pin "1") (pinfunction "1_1") (pintype "passive"))
      (node (ref "J1") (pin "2") (pinfunction "2_2") (pintype "passive"))
      (node (ref "R1") (pin "1") (pinfunction "1_1") (pintype "passive"))
      (node (ref "R11") (pin "1") (pinfunction "1_1") (pintype "passive"))
      (node (ref "R18") (pin "1") (pinfunction "1_1") (pintype "passive"))
      (node (ref "R19") (pin "2") (pinfunction "2_2") (pintype "passive"))
      (node (ref "R21") (pin "1") (pinfunction "1_1") (pintype "passive"))
      (node (ref "R23") (pin "1") (pinfunction "1_1") (pintype "passive"))
      (node (ref "R23") (pin "2") (pinfunction "2_2") (pintype "passive"))
      (node (ref "R24") (pin "2") (pinfunction "2_2") (pintype "passive"))
      (node (ref "R39") (pin "2") (pinfunction "2_2") (pintype "passive"))
      (node (ref "R43") (pin "1") (pinfunction "1_1") (pintype "passive"))
      (node (ref "R43") (pin "2") (pinfunction "2_2") (pintype "passive"))
      (node (ref "R44") (pin "1") (pinfunction "1_1") (pintype "passive"))
      (node (ref "R44") (pin "2") (pinfunction "2_2") (pintype "passive"))
      (node (ref "R5") (pin "1") (pinfunction "1_1") (pintype "passive"))
      (node (ref "U1") (pin "8") (pinfunction "V+_8") (pintype "passive"))
      (node (ref "U2") (pin "8") (pinfunction "V+_8") (pintype "passive"))
      (node (ref "U3") (pin "1") (pinfunction "VDD_1") (pintype "passive"))
      (node (ref "U3") (pin "17") (pinfunction "INT/CCP3/C1OUT/AN2/RA2_17") (pintype "passive"))
      (node (ref "U5") (pin "1") (pinfunction "Vcc_1") (pintype "passive"))
      (node (ref "U7") (pin "3") (pinfunction "Vout_3") (pintype "passive"))
    )
    (net (code "39") (name "/VCC_DRV") (class "Default")
      (node (ref "C27") (pin "1") (pinfunction "1_1") (pintype "passive"))
      (node (ref "R37") (pin "1") (pinfunction "1_1") (pintype "passive"))
      (node (ref "R37") (pin "2") (pinfunction "2_2") (pintype "passive"))
      (node (ref "U3") (pin "11") (pinfunction "SCL1/SCK1/RB6_11") (pintype "passive"))
      (node (ref "U6") (pin "6") (pinfunction "Vcc_6") (pintype "passive"))
    )
    (net (code "40") (name "/VIN") (class "Default")
      (node (ref "C22") (pin "1") (pinfunction "1_1") (pintype "passive"))
      (node (ref "R12") (pin "1") (pinfunction "1_1") (pintype "passive"))
      (node (ref "R8") (pin "2") (pinfunction "2_2") (pintype "passive"))
      (node (ref "U3") (pin "12") (pinfunction "DT/RX/AN11/RB5_12") (pintype "passive"))
    )
    (net (code "41") (name "/VOUT") (class "Default")
      (node (ref "C23") (pin "1") (pinfunction "1_1") (pintype "passive"))
      (node (ref "R13") (pin "1") (pinfunction "1_1") (pintype "passive"))
      (node (ref "R9") (pin "2") (pinfunction "2_2") (pintype "passive"))
      (node (ref "U3") (pin "13") (pinfunction "SDI1/SDA1/AN10/RB4_13") (pintype "passive"))
    )
    (net (code "42") (name "Net-(C40-Pad1)") (class "Default")
      (node (ref "C40") (pin "1") (pinfunction "1_1") (pintype "passive"))
      (node (ref "R31") (pin "1") (pinfunction "1_1") (pintype "passive"))
      (node (ref "R32") (pin "2") (pinfunction "2_2") (pintype "passive"))
    )
    (net (code "43") (name "Net-(U1A-IN+)") (class "Default")
      (node (ref "R2") (pin "1") (pinfunction "1_1") (pintype "passive"))
      (node (ref "U1") (pin "3") (pinfunction "IN+_3") (pintype "passive"))
    )
    (net (code "44") (name "Net-(U1A-IN-)") (class "Default")
      (node (ref "R6") (pin "2") (pinfunction "2_2") (pintype "passive"))
      (node (ref "R7") (pin "1") (pinfunction "1_1") (pintype "passive"))
      (node (ref "U1") (pin "2") (pinfunction "IN-_2") (pintype "passive"))
    )
    (net (code "45") (name "Net-(U2B-IN+)") (class "Default")
      (node (ref "R45") (pin "2") (pinfunction "2_2") (pintype "passive"))
      (node (ref "U2") (pin "5") (pinfunction "IN+_5") (pintype "passive"))
    )
    (net (code "46") (name "Net-(U2B-IN-)") (class "Default")
      (node (ref "R46") (pin "2") (pinfunction "2_2") (pintype "passive"))
      (node (ref "U2") (pin "6") (pinfunction "IN-_6") (pintype "passive"))
    )
    (net (code "47") (name "SGND") (class "Default")
      (node (ref "C11") (pin "2") (pinfunction "2_2") (pintype "passive"))
      (node (ref "C12") (pin "2") (pinfunction "2_2") (pintype "passive"))
      (node (ref "C18") (pin "2") (pinfunction "2_2") (pintype "passive"))
      (node (ref "C19") (pin "2") (pinfunction "2_2") (pintype "passive"))
      (node (ref "C2") (pin "2") (pinfunction "2_2") (pintype "passive"))
      (node (ref "C21") (pin "2") (pinfunction "2_2") (pintype "passive"))
      (node (ref "C22") (pin "2") (pinfunction "2_2") (pintype "passive"))
      (node (ref "C23") (pin "2") (pinfunction "2_2") (pintype "passive"))
      (node (ref "C24") (pin "2") (pinfunction "2_2") (pintype "passive"))
      (node (ref "C36") (pin "2") (pinfunction "2_2") (pintype "passive"))
      (node (ref "C37") (pin "2") (pinfunction "2_2") (pintype "passive"))
      (node (ref "C4") (pin "2") (pinfunction "2_2") (pintype "passive"))
      (node (ref "C40") (pin "2") (pinfunction "2_2") (pintype "passive"))
      (node (ref "C41") (pin "2") (pinfunction "2_2") (pintype "passive"))
      (node (ref "C43") (pin "2") (pinfunction "2_2") (pintype "passive"))
      (node (ref "C5") (pin "1") (pinfunction "1_1") (pintype "passive"))
      (node (ref "C7") (pin "2") (pinfunction "2_2") (pintype "passive"))
      (node (ref "C8") (pin "2") (pinfunction "2_2") (pintype "passive"))
      (node (ref "D2") (pin "1") (pinfunction "A_1") (pintype "passive"))
      (node (ref "J1") (pin "3") (pinfunction "3_3") (pintype "passive"))
      (node (ref "J3") (pin "2") (pinfunction "2_2") (pintype "passive"))
      (node (ref "J6") (pin "2") (pinfunction "2_2") (pintype "passive"))
      (node (ref "JP1") (pin "1") (pinfunction "1_1") (pintype "passive"))
      (node (ref "JP1") (pin "12") (pinfunction "12_12") (pintype "passive"))
      (node (ref "JP1") (pin "8") (pinfunction "8_8") (pintype "passive"))
      (node (ref "R12") (pin "2") (pinfunction "2_2") (pintype "passive"))
      (node (ref "R13") (pin "2") (pinfunction "2_2") (pintype "passive"))
      (node (ref "R27") (pin "1") (pinfunction "1_1") (pintype "passive"))
      (node (ref "R3") (pin "1") (pinfunction "1_1") (pintype "passive"))
      (node (ref "R30") (pin "1") (pinfunction "1_1") (pintype "passive"))
      (node (ref "R33") (pin "1") (pinfunction "1_1") (pintype "passive"))
      (node (ref "R36") (pin "1") (pinfunction "1_1") (pintype "passive"))
      (node (ref "R45") (pin "1") (pinfunction "1_1") (pintype "passive"))
      (node (ref "R46") (pin "1") (pinfunction "1_1") (pintype "passive"))
      (node (ref "R47") (pin "1") (pinfunction "1_1") (pintype "passive"))
      (node (ref "R47") (pin "2") (pinfunction "2_2") (pintype "passive"))
      (node (ref "R48") (pin "1") (pinfunction "1_1") (pintype "passive"))
      (node (ref "R48") (pin "2") (pinfunction "2_2") (pintype "passive"))
      (node (ref "R7") (pin "2") (pinfunction "2_2") (pintype "passive"))
      (node (ref "U1") (pin "4") (pinfunction "V-_4") (pintype "passive"))
      (node (ref "U2") (pin "4") (pinfunction "V-_4") (pintype "passive"))
      (node (ref "U3") (pin "20") (pinfunction "VSS_20") (pintype "passive"))
      (node (ref "U5") (pin "2") (pinfunction "GND_2") (pintype "passive"))
      (node (ref "U7") (pin "2") (pinfunction "GND_2") (pintype "passive"))
    )
    (net (code "48") (name "unconnected-(U1B-V+-Pad8)") (class "Default")
      (node (ref "U1") (pin "8") (pinfunction "V+_8") (pintype "passive"))
    )
    (net (code "49") (name "unconnected-(U1B-V--Pad4)") (class "Default")
      (node (ref "U1") (pin "4") (pinfunction "V-_4") (pintype "passive"))
    )
    (net (code "50") (name "unconnected-(U2B-OUT-Pad7)") (class "Default")
      (node (ref "U2") (pin "7") (pinfunction "OUT_7") (pintype "passive"))
    )
    (net (code "51") (name "unconnected-(U2B-V+-Pad8)") (class "Default")
      (node (ref "U2") (pin "8") (pinfunction "V+_8") (pintype "passive"))
    )
    (net (code "52") (name "unconnected-(U2B-V--Pad4)") (class "Default")
      (node (ref "U2") (pin "4") (pinfunction "V-_4") (pintype "passive"))
    )
    (net (code "53") (name "unconnected-(U3-RA5{slash}CLKIN-Pad2)") (class "Default")
      (node (ref "U3") (pin "2") (pinfunction "RA5/CLKIN_2") (pintype "passive"))
    )
    (net (code "54") (name "unconnected-(U3-RB7{slash}TX{slash}CK-Pad10)") (class "Default")
      (node (ref "U3") (pin "10") (pinfunction "RB7/TX/CK_10") (pintype "passive"))
    )
  )
)
